# Power_Supply.net
KiCad netlist of a schematic drawn in Altium Designer
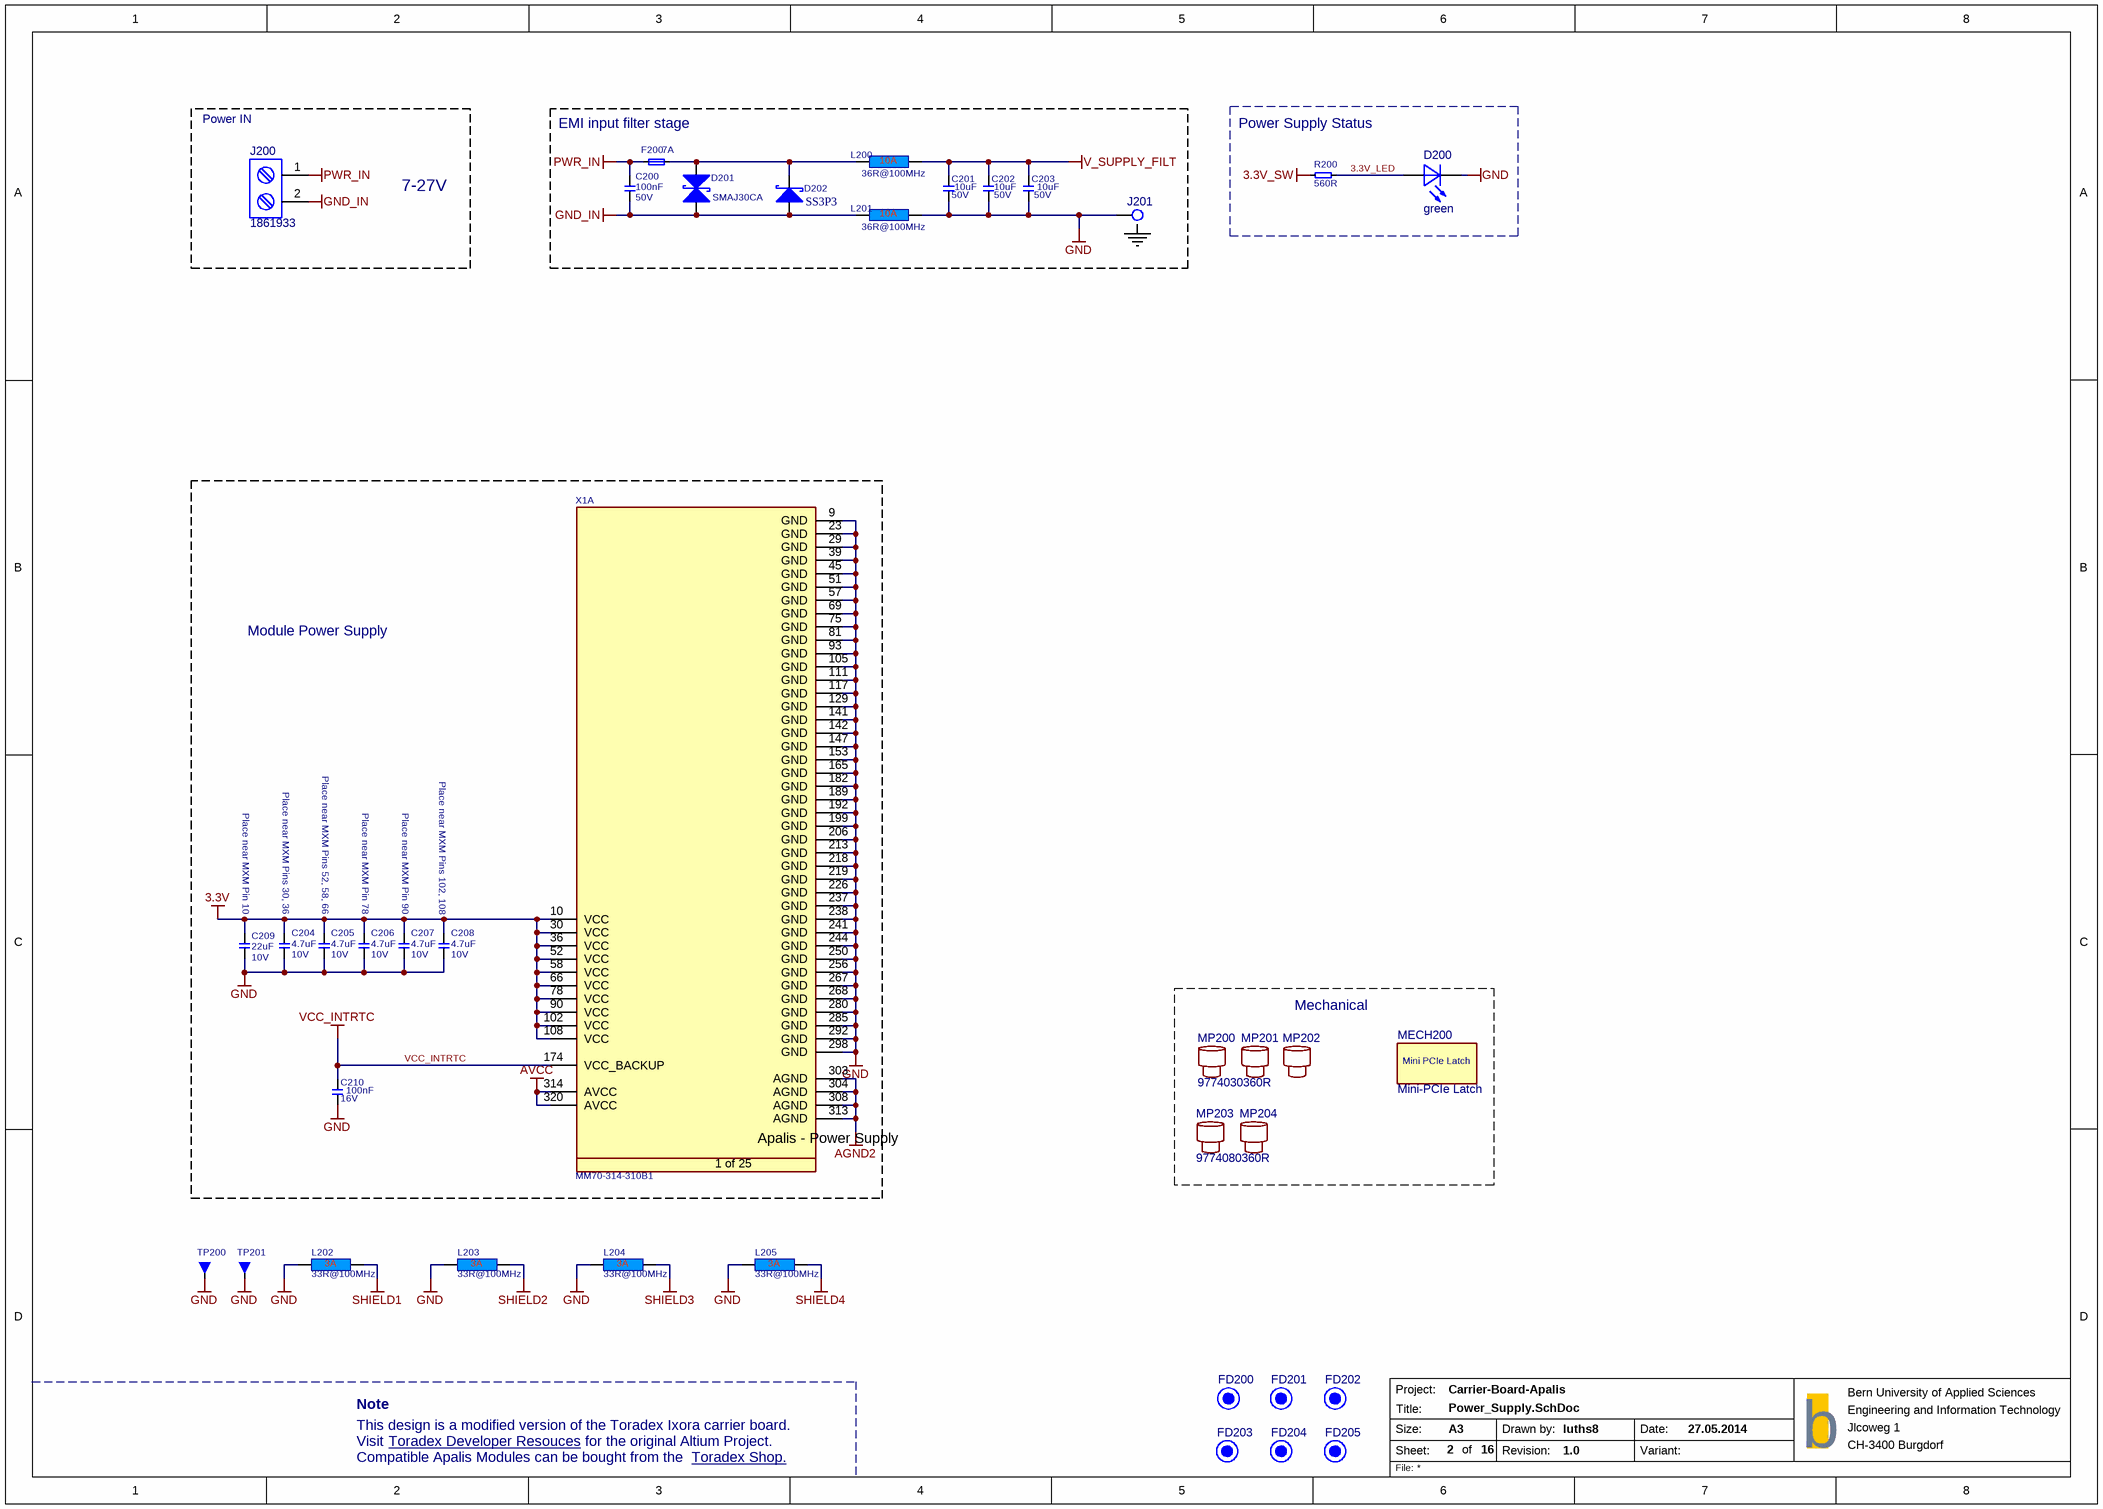
[diagram p0: Power_Supply.SchDoc]

(export (version "E")
  (design (tool "Eeschema 10.0.6"))
  (components
    (comp (ref "C200")
      (value "100nF")
      (footprint "SMD0603CAP")
      (description "Capacitor Ceramic X7R 100nF 50V 20% 0603")
      (fields (field (name "TOLERANCE") "20%") (field (name "RATING") "50V"))
      (libsource (lib "Ixora") (part "C-X7R-100nF-50V-20%-0603"))
    )
    (comp (ref "C201")
      (value "10uF")
      (footprint "SMD1210CAP")
      (description "Capacitor Ceramic X5R 10uF 50V 20% 1210")
      (fields (field (name "TOLERANCE") "20%") (field (name "RATING") "50V"))
      (libsource (lib "Ixora") (part "C-X5R-10uF-50V-20%-1210"))
    )
    (comp (ref "C202")
      (value "10uF")
      (footprint "SMD1210CAP")
      (description "Capacitor Ceramic X5R 10uF 50V 20% 1210")
      (fields (field (name "TOLERANCE") "20%") (field (name "RATING") "50V"))
      (libsource (lib "Ixora") (part "C-X5R-10uF-50V-20%-1210"))
    )
    (comp (ref "C203")
      (value "10uF")
      (footprint "SMD1210CAP")
      (description "Capacitor Ceramic X5R 10uF 50V 20% 1210")
      (fields (field (name "TOLERANCE") "20%") (field (name "RATING") "50V"))
      (libsource (lib "Ixora") (part "C-X5R-10uF-50V-20%-1210"))
    )
    (comp (ref "C204")
      (value "4.7uF")
      (footprint "SMD0603CAP")
      (description "Capacitor Ceramic X5R 4.7uF 10V 10% 0603")
      (fields (field (name "TOLERANCE") "10%") (field (name "RATING") "10V"))
      (libsource (lib "Ixora") (part "C-X5R-4.7uF-10V-10%-0603"))
    )
    (comp (ref "C205")
      (value "4.7uF")
      (footprint "SMD0603CAP")
      (description "Capacitor Ceramic X5R 4.7uF 10V 10% 0603")
      (fields (field (name "TOLERANCE") "10%") (field (name "RATING") "10V"))
      (libsource (lib "Ixora") (part "C-X5R-4.7uF-10V-10%-0603"))
    )
    (comp (ref "C206")
      (value "4.7uF")
      (footprint "SMD0603CAP")
      (description "Capacitor Ceramic X5R 4.7uF 10V 10% 0603")
      (fields (field (name "TOLERANCE") "10%") (field (name "RATING") "10V"))
      (libsource (lib "Ixora") (part "C-X5R-4.7uF-10V-10%-0603"))
    )
    (comp (ref "C207")
      (value "4.7uF")
      (footprint "SMD0603CAP")
      (description "Capacitor Ceramic X5R 4.7uF 10V 10% 0603")
      (fields (field (name "TOLERANCE") "10%") (field (name "RATING") "10V"))
      (libsource (lib "Ixora") (part "C-X5R-4.7uF-10V-10%-0603"))
    )
    (comp (ref "C208")
      (value "4.7uF")
      (footprint "SMD0603CAP")
      (description "Capacitor Ceramic X5R 4.7uF 10V 10% 0603")
      (fields (field (name "TOLERANCE") "10%") (field (name "RATING") "10V"))
      (libsource (lib "Ixora") (part "C-X5R-4.7uF-10V-10%-0603"))
    )
    (comp (ref "C209")
      (value "22uF")
      (footprint "SMD0805CAP")
      (description "Capacitor Ceramic X5R 22uF 10V 20% 0805")
      (fields (field (name "TOLERANCE") "20%") (field (name "RATING") "10V"))
      (libsource (lib "Ixora") (part "C-X5R-22uF-10V-20%-0805"))
    )
    (comp (ref "C210")
      (value "100nF")
      (footprint "SMD0603CAP")
      (description "Capacitor Ceramic X7R 100nF 16V 10% 0603")
      (fields (field (name "TOLERANCE") "10%") (field (name "RATING") "16V"))
      (libsource (lib "Ixora") (part "C-X7R-100nF-16V-10%-0402"))
    )
    (comp (ref "D200")
      (value "green")
      (footprint "LED")
      (description "LED green")
      (fields (field (name "MANUFACTURER PART NO.") "LGM67KG1J224Z"))
      (libsource (lib "Audio-Streamer") (part "LED green"))
    )
    (comp (ref "D201")
      (value "D-Littelfuse-SMAJ30CA-Schottky")
      (footprint "T_LITTLEFUSE_SMAJ30CA")
      (description "Bidirectional ESD protection")
      (fields (field (name "MANUFACTURER PART NO.") "SMAJ30CA"))
      (libsource (lib "Ixora") (part "D-Littelfuse-SMAJ30CA-Schottky"))
    )
    (comp (ref "D202")
      (value "SS3P3")
      (footprint "T_VISHAY_SS3P3")
      (description "SS3P3-E3/84A Schottky Diode")
      (fields (field (name "MANUFACTURER PART NO.") "SS3P3-E3/84A"))
      (libsource (lib "Ixora") (part "D-Vishay-SS3P3-E3/84A-Schottky"))
    )
    (comp (ref "F200")
      (value "7A")
      (footprint "T_Littelfuse_0458")
      (description "Fuse 7A Fast")
      (fields (field (name "MANUFACTURER PART NO.") "0458007"))
      (libsource (lib "Ixora") (part "F-Littelfuse-0458007"))
    )
    (comp (ref "FD200")
      (value "Fiducial")
      (footprint "FIDUCIAL")
      (description "Fiducial Marker")
      (libsource (lib "Audio-Streamer") (part "Fiducial"))
    )
    (comp (ref "FD201")
      (value "Fiducial")
      (footprint "FIDUCIAL")
      (description "Fiducial Marker")
      (libsource (lib "Audio-Streamer") (part "Fiducial"))
    )
    (comp (ref "FD202")
      (value "Fiducial")
      (footprint "FIDUCIAL")
      (description "Fiducial Marker")
      (libsource (lib "Audio-Streamer") (part "Fiducial"))
    )
    (comp (ref "FD203")
      (value "Fiducial")
      (footprint "FIDUCIAL")
      (description "Fiducial Marker")
      (libsource (lib "Audio-Streamer") (part "Fiducial"))
    )
    (comp (ref "FD204")
      (value "Fiducial")
      (footprint "FIDUCIAL")
      (description "Fiducial Marker")
      (libsource (lib "Audio-Streamer") (part "Fiducial"))
    )
    (comp (ref "FD205")
      (value "Fiducial")
      (footprint "FIDUCIAL")
      (description "Fiducial Marker")
      (libsource (lib "Audio-Streamer") (part "Fiducial"))
    )
    (comp (ref "J200")
      (value "1861933")
      (footprint "1861933")
      (description "Screw Terminal, 2 Position, 5mm Spacing")
      (libsource (lib "Audio-Streamer") (part "1861933"))
    )
    (comp (ref "J201")
      (value "Solder Pin")
      (footprint "SOLDER_PIN")
      (libsource (lib "Audio-Streamer") (part "Solder Pin"))
    )
    (comp (ref "L200")
      (value "36R@100MHz")
      (footprint "T_Laird_35F0121-0SR-10")
      (description "Power Supply FB 10A")
      (fields (field (name "TOLERANCE") "25%"))
      (libsource (lib "Ixora") (part "L-Laird-35F0121-0SR-10-10A-25%"))
    )
    (comp (ref "L201")
      (value "36R@100MHz")
      (footprint "T_Laird_35F0121-0SR-10")
      (description "Power Supply FB 10A")
      (fields (field (name "TOLERANCE") "25%"))
      (libsource (lib "Ixora") (part "L-Laird-35F0121-0SR-10-10A-25%"))
    )
    (comp (ref "L202")
      (value "33R@100MHz")
      (footprint "INDC1608X95N")
      (description "33R@100MHz 3A EMI FILTER")
      (fields (field (name "TOLERANCE") "25%"))
      (libsource (lib "Ixora") (part "L-33R@100MHz-3A-25%-0603"))
    )
    (comp (ref "L203")
      (value "33R@100MHz")
      (footprint "INDC1608X95N")
      (description "33R@100MHz 3A EMI FILTER")
      (fields (field (name "TOLERANCE") "25%"))
      (libsource (lib "Ixora") (part "L-33R@100MHz-3A-25%-0603"))
    )
    (comp (ref "L204")
      (value "33R@100MHz")
      (footprint "INDC1608X95N")
      (description "33R@100MHz 3A EMI FILTER")
      (fields (field (name "TOLERANCE") "25%"))
      (libsource (lib "Ixora") (part "L-33R@100MHz-3A-25%-0603"))
    )
    (comp (ref "L205")
      (value "33R@100MHz")
      (footprint "INDC1608X95N")
      (description "33R@100MHz 3A EMI FILTER")
      (fields (field (name "TOLERANCE") "25%"))
      (libsource (lib "Ixora") (part "L-33R@100MHz-3A-25%-0603"))
    )
    (comp (ref "MECH200")
      (value "Mini-PCIe Latch")
      (footprint "T_Molex_48099-5701")
      (fields (field (name "MANUFACTURER PART NO.") "48099-5701"))
      (libsource (lib "Ixora") (part "MECH-Molex-48099-5701"))
    )
    (comp (ref "MP200")
      (value "9774030360R")
      (description "Spacer M3 SMD")
      (libsource (lib "Audio-Streamer") (part "Spacer M3 SMD"))
    )
    (comp (ref "MP201")
      (value "9774030360R")
      (description "Spacer M3 SMD")
      (libsource (lib "Audio-Streamer") (part "Spacer M3 SMD"))
    )
    (comp (ref "MP202")
      (value "9774030360R")
      (description "Spacer M3 SMD")
      (libsource (lib "Audio-Streamer") (part "Spacer M3 SMD"))
    )
    (comp (ref "MP203")
      (value "9774080360R")
      (description "Spacer M3 SMD")
      (libsource (lib "Audio-Streamer") (part "Spacer M3 SMD"))
    )
    (comp (ref "MP204")
      (value "9774080360R")
      (description "Spacer M3 SMD")
      (libsource (lib "Audio-Streamer") (part "Spacer M3 SMD"))
    )
    (comp (ref "R200")
      (value "560R")
      (footprint "SMD0603RES")
      (description "Resistor 560 ohm 63mW 5% 0603")
      (fields (field (name "TOLERANCE") "5%"))
      (libsource (lib "Ixora") (part "R-560R-63mW-5%-0402"))
    )
    (comp (ref "TP200")
      (value "5011")
      (footprint "T_TP-THT - EYE")
      (description "Testpin Eye TH")
      (libsource (lib "Ixora") (part "TP-Keystone-5011"))
    )
    (comp (ref "TP201")
      (value "5011")
      (footprint "T_TP-THT - EYE")
      (description "Testpin Eye TH")
      (libsource (lib "Ixora") (part "TP-Keystone-5011"))
    )
    (comp (ref "X1")
      (value "CON-JAE-MM70-314-310B1-314-0.5mm")
      (footprint "T_JAE_MM70-314-310B1")
      (description "MXM3 Connector")
      (fields (field (name "MANUFACTURER PART NO.") "MM70-314-310B1"))
      (libsource (lib "Ixora") (part "CON-JAE-MM70-314-310B1-314-0.5mm"))
    )
  )
  (nets
    (net (code "1") (name "/3.3V_LED") (class "Default")
      (node (ref "D200") (pin "A") (pinfunction "A_A") (pintype "passive"))
      (node (ref "R200") (pin "2") (pinfunction "2_2") (pintype "passive"))
    )
    (net (code "2") (name "3.3V") (class "Default")
      (node (ref "C204") (pin "1") (pinfunction "1_1") (pintype "passive"))
      (node (ref "C205") (pin "1") (pinfunction "1_1") (pintype "passive"))
      (node (ref "C206") (pin "1") (pinfunction "1_1") (pintype "passive"))
      (node (ref "C207") (pin "1") (pinfunction "1_1") (pintype "passive"))
      (node (ref "C208") (pin "1") (pinfunction "1_1") (pintype "passive"))
      (node (ref "C209") (pin "1") (pinfunction "1_1") (pintype "passive"))
      (node (ref "X1") (pin "10") (pinfunction "VCC_10") (pintype "passive"))
      (node (ref "X1") (pin "102") (pinfunction "VCC_102") (pintype "passive"))
      (node (ref "X1") (pin "108") (pinfunction "VCC_108") (pintype "passive"))
      (node (ref "X1") (pin "30") (pinfunction "VCC_30") (pintype "passive"))
      (node (ref "X1") (pin "36") (pinfunction "VCC_36") (pintype "passive"))
      (node (ref "X1") (pin "52") (pinfunction "VCC_52") (pintype "passive"))
      (node (ref "X1") (pin "58") (pinfunction "VCC_58") (pintype "passive"))
      (node (ref "X1") (pin "66") (pinfunction "VCC_66") (pintype "passive"))
      (node (ref "X1") (pin "78") (pinfunction "VCC_78") (pintype "passive"))
      (node (ref "X1") (pin "90") (pinfunction "VCC_90") (pintype "passive"))
    )
    (net (code "3") (name "3.3V_SW") (class "Default")
      (node (ref "R200") (pin "1") (pinfunction "1_1") (pintype "passive"))
    )
    (net (code "4") (name "AGND2") (class "Default")
      (node (ref "X1") (pin "303") (pinfunction "AGND_303") (pintype "power_in"))
      (node (ref "X1") (pin "304") (pinfunction "AGND_304") (pintype "power_in"))
      (node (ref "X1") (pin "308") (pinfunction "AGND_308") (pintype "power_in"))
      (node (ref "X1") (pin "313") (pinfunction "AGND_313") (pintype "passive"))
    )
    (net (code "5") (name "AVCC") (class "Default")
      (node (ref "X1") (pin "314") (pinfunction "AVCC_314") (pintype "power_in"))
      (node (ref "X1") (pin "320") (pinfunction "AVCC_320") (pintype "passive"))
    )
    (net (code "6") (name "GND") (class "Default")
      (node (ref "C201") (pin "1") (pinfunction "1_1") (pintype "passive"))
      (node (ref "C202") (pin "1") (pinfunction "1_1") (pintype "passive"))
      (node (ref "C203") (pin "1") (pinfunction "1_1") (pintype "passive"))
      (node (ref "C204") (pin "2") (pinfunction "2_2") (pintype "passive"))
      (node (ref "C205") (pin "2") (pinfunction "2_2") (pintype "passive"))
      (node (ref "C206") (pin "2") (pinfunction "2_2") (pintype "passive"))
      (node (ref "C207") (pin "2") (pinfunction "2_2") (pintype "passive"))
      (node (ref "C208") (pin "2") (pinfunction "2_2") (pintype "passive"))
      (node (ref "C209") (pin "2") (pinfunction "2_2") (pintype "passive"))
      (node (ref "C210") (pin "1") (pinfunction "1_1") (pintype "passive"))
      (node (ref "D200") (pin "C") (pinfunction "C_C") (pintype "passive"))
      (node (ref "J201") (pin "1") (pinfunction "1_1") (pintype "passive"))
      (node (ref "L201") (pin "2") (pinfunction "2_2") (pintype "passive"))
      (node (ref "L202") (pin "1") (pinfunction "1_1") (pintype "passive"))
      (node (ref "L203") (pin "1") (pinfunction "1_1") (pintype "passive"))
      (node (ref "L204") (pin "1") (pinfunction "1_1") (pintype "passive"))
      (node (ref "L205") (pin "1") (pinfunction "1_1") (pintype "passive"))
      (node (ref "TP200") (pin "1") (pinfunction "1_1") (pintype "passive"))
      (node (ref "TP201") (pin "1") (pinfunction "1_1") (pintype "passive"))
      (node (ref "X1") (pin "105") (pinfunction "GND_105") (pintype "power_in"))
      (node (ref "X1") (pin "111") (pinfunction "GND_111") (pintype "power_in"))
      (node (ref "X1") (pin "117") (pinfunction "GND_117") (pintype "power_in"))
      (node (ref "X1") (pin "129") (pinfunction "GND_129") (pintype "power_in"))
      (node (ref "X1") (pin "141") (pinfunction "GND_141") (pintype "power_in"))
      (node (ref "X1") (pin "142") (pinfunction "GND_142") (pintype "power_in"))
      (node (ref "X1") (pin "147") (pinfunction "GND_147") (pintype "power_in"))
      (node (ref "X1") (pin "153") (pinfunction "GND_153") (pintype "power_in"))
      (node (ref "X1") (pin "165") (pinfunction "GND_165") (pintype "power_in"))
      (node (ref "X1") (pin "182") (pinfunction "GND_182") (pintype "power_in"))
      (node (ref "X1") (pin "189") (pinfunction "GND_189") (pintype "power_in"))
      (node (ref "X1") (pin "192") (pinfunction "GND_192") (pintype "power_in"))
      (node (ref "X1") (pin "199") (pinfunction "GND_199") (pintype "power_in"))
      (node (ref "X1") (pin "206") (pinfunction "GND_206") (pintype "power_in"))
      (node (ref "X1") (pin "213") (pinfunction "GND_213") (pintype "power_in"))
      (node (ref "X1") (pin "218") (pinfunction "GND_218") (pintype "power_in"))
      (node (ref "X1") (pin "219") (pinfunction "GND_219") (pintype "power_in"))
      (node (ref "X1") (pin "226") (pinfunction "GND_226") (pintype "power_in"))
      (node (ref "X1") (pin "23") (pinfunction "GND_23") (pintype "passive"))
      (node (ref "X1") (pin "237") (pinfunction "GND_237") (pintype "power_in"))
      (node (ref "X1") (pin "238") (pinfunction "GND_238") (pintype "power_in"))
      (node (ref "X1") (pin "241") (pinfunction "GND_241") (pintype "power_in"))
      (node (ref "X1") (pin "244") (pinfunction "GND_244") (pintype "power_in"))
      (node (ref "X1") (pin "250") (pinfunction "GND_250") (pintype "power_in"))
      (node (ref "X1") (pin "256") (pinfunction "GND_256") (pintype "power_in"))
      (node (ref "X1") (pin "267") (pinfunction "GND_267") (pintype "power_in"))
      (node (ref "X1") (pin "268") (pinfunction "GND_268") (pintype "power_in"))
      (node (ref "X1") (pin "280") (pinfunction "GND_280") (pintype "power_in"))
      (node (ref "X1") (pin "285") (pinfunction "GND_285") (pintype "power_in"))
      (node (ref "X1") (pin "29") (pinfunction "GND_29") (pintype "power_in"))
      (node (ref "X1") (pin "292") (pinfunction "GND_292") (pintype "power_in"))
      (node (ref "X1") (pin "298") (pinfunction "GND_298") (pintype "power_in"))
      (node (ref "X1") (pin "39") (pinfunction "GND_39") (pintype "power_in"))
      (node (ref "X1") (pin "45") (pinfunction "GND_45") (pintype "power_in"))
      (node (ref "X1") (pin "51") (pinfunction "GND_51") (pintype "power_in"))
      (node (ref "X1") (pin "57") (pinfunction "GND_57") (pintype "power_in"))
      (node (ref "X1") (pin "69") (pinfunction "GND_69") (pintype "power_in"))
      (node (ref "X1") (pin "75") (pinfunction "GND_75") (pintype "power_in"))
      (node (ref "X1") (pin "81") (pinfunction "GND_81") (pintype "power_in"))
      (node (ref "X1") (pin "9") (pinfunction "GND_9") (pintype "passive"))
      (node (ref "X1") (pin "93") (pinfunction "GND_93") (pintype "power_in"))
    )
    (net (code "7") (name "GND_IN") (class "Default")
      (node (ref "C200") (pin "1") (pinfunction "1_1") (pintype "passive"))
      (node (ref "D201") (pin "2") (pinfunction "Anode_2") (pintype "passive"))
      (node (ref "D202") (pin "2") (pinfunction "2_2") (pintype "passive"))
      (node (ref "J200") (pin "2") (pinfunction "2_2") (pintype "passive"))
      (node (ref "L201") (pin "1") (pinfunction "1_1") (pintype "passive"))
    )
    (net (code "8") (name "Net-(D201-Cathode)") (class "Default")
      (node (ref "D201") (pin "1") (pinfunction "Cathode_1") (pintype "passive"))
      (node (ref "D202") (pin "1") (pinfunction "1_1") (pintype "passive"))
      (node (ref "F200") (pin "2") (pinfunction "2_2") (pintype "passive"))
      (node (ref "L200") (pin "1") (pinfunction "1_1") (pintype "passive"))
    )
    (net (code "9") (name "PWR_IN") (class "Default")
      (node (ref "C200") (pin "2") (pinfunction "2_2") (pintype "passive"))
      (node (ref "F200") (pin "1") (pinfunction "1_1") (pintype "passive"))
      (node (ref "J200") (pin "1") (pinfunction "1_1") (pintype "passive"))
    )
    (net (code "10") (name "SHIELD1") (class "Default")
      (node (ref "L202") (pin "2") (pinfunction "2_2") (pintype "passive"))
    )
    (net (code "11") (name "SHIELD2") (class "Default")
      (node (ref "L203") (pin "2") (pinfunction "2_2") (pintype "passive"))
    )
    (net (code "12") (name "SHIELD3") (class "Default")
      (node (ref "L204") (pin "2") (pinfunction "2_2") (pintype "passive"))
    )
    (net (code "13") (name "SHIELD4") (class "Default")
      (node (ref "L205") (pin "2") (pinfunction "2_2") (pintype "passive"))
    )
    (net (code "14") (name "VCC_INTRTC") (class "Default")
      (node (ref "C210") (pin "2") (pinfunction "2_2") (pintype "passive"))
      (node (ref "X1") (pin "174") (pinfunction "VCC_BACKUP_174") (pintype "passive"))
    )
    (net (code "15") (name "V_SUPPLY_FILT") (class "Default")
      (node (ref "C201") (pin "2") (pinfunction "2_2") (pintype "passive"))
      (node (ref "C202") (pin "2") (pinfunction "2_2") (pintype "passive"))
      (node (ref "C203") (pin "2") (pinfunction "2_2") (pintype "passive"))
      (node (ref "L200") (pin "2") (pinfunction "2_2") (pintype "passive"))
    )
  )
)
